# Esquematico.net
KiCad netlist of a schematic drawn in Altium Designer
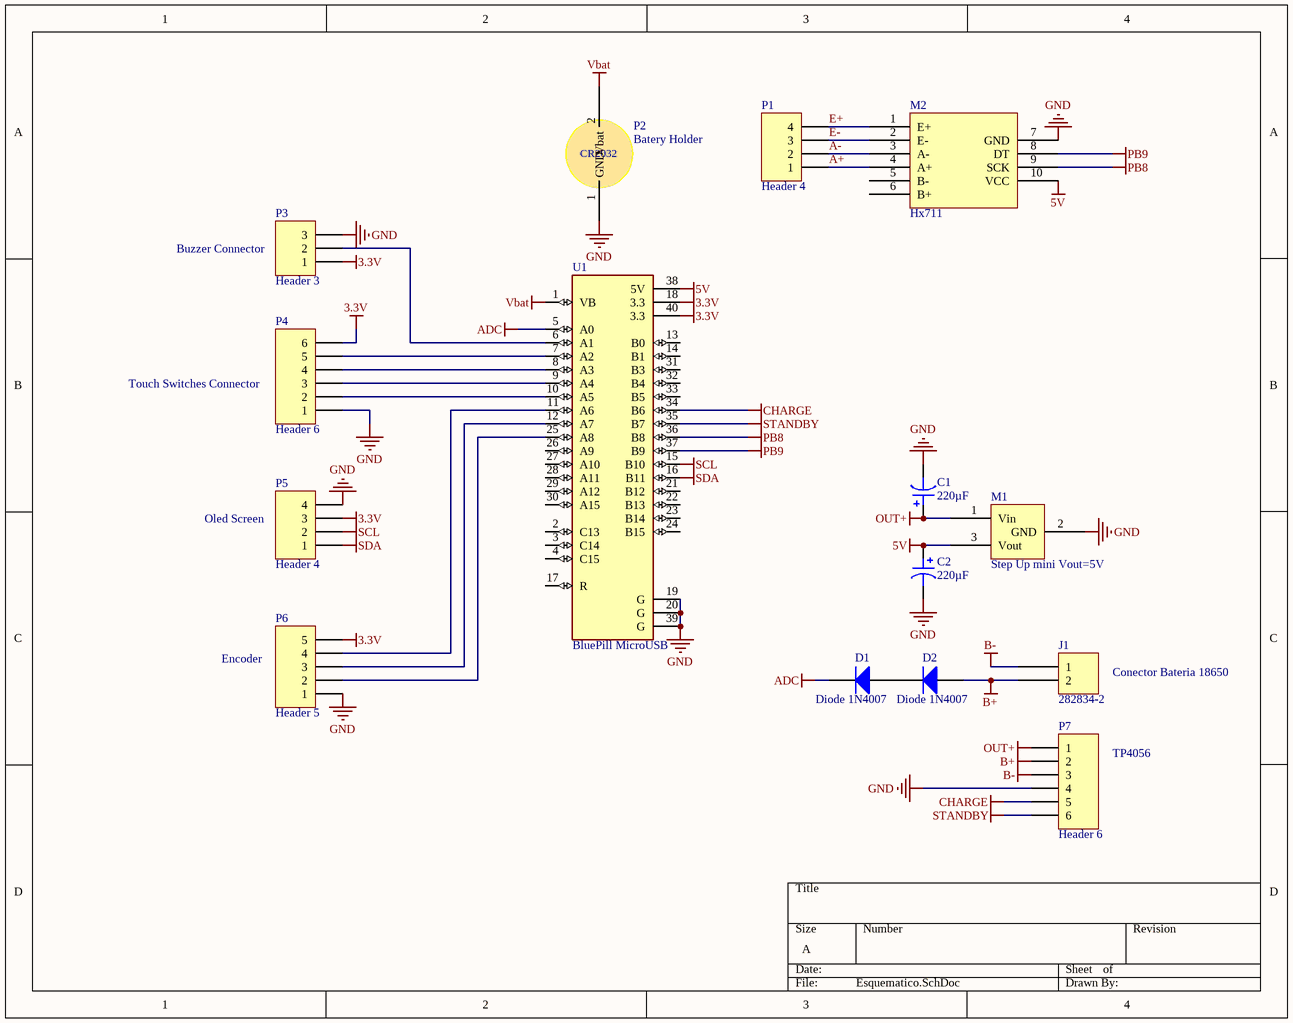
[diagram p0: Esquematico.SchDoc]

(export (version "E")
  (design (tool "Eeschema 10.0.6"))
  (components
    (comp (ref "C1")
      (value "220µF")
      (footprint "CAP TH ALUM ELEC D10.00mm S5.00mm H12.50mm")
      (description "CAP ALUM 220UF 20% 50V RADIAL")
      (fields (field (name "PART NUMBER") "UVZ1H221MPD") (field (name "MANUFACTURER") "Nichicon"))
      (libsource (lib "Celestial Altium Library - altium_library") (part "Polarised Capacitor"))
    )
    (comp (ref "C2")
      (value "220µF")
      (footprint "CAP TH ALUM ELEC D10.00mm S5.00mm H12.50mm")
      (description "CAP ALUM 220UF 20% 50V RADIAL")
      (fields (field (name "PART NUMBER") "UVZ1H221MPD") (field (name "MANUFACTURER") "Nichicon"))
      (libsource (lib "Celestial Altium Library - altium_library") (part "Polarised Capacitor"))
    )
    (comp (ref "D1")
      (value "Diode 1N4007")
      (footprint "DO-41")
      (description "1 Amp General Purpose Rectifier")
      (fields (field (name "PUBLISHER") "Altium Limited"))
      (libsource (lib "Miscellaneous Devices") (part "Diode 1N4007"))
    )
    (comp (ref "D2")
      (value "Diode 1N4007")
      (footprint "DO-41")
      (description "1 Amp General Purpose Rectifier")
      (fields (field (name "PUBLISHER") "Altium Limited"))
      (libsource (lib "Miscellaneous Devices") (part "Diode 1N4007"))
    )
    (comp (ref "J1")
      (value "282834-2")
      (footprint "TE 282834-2")
      (description "TERM BLK 2P SIDE ENT 2.54MM PCB")
      (fields (field (name "MANUFACTURER") "TE Connectivity AMP Connectors") (field (name "VOLTAGE") "150V"))
      (libsource (lib "Celestial Altium Library - altium_library") (part "2 Pin"))
    )
    (comp (ref "M1")
      (value "Step Up mini Vout=5V")
      (footprint "StepUp Mini 5V")
      (libsource (lib "BateryHolder") (part "StepUp 5V"))
    )
    (comp (ref "M2") (value "Hx711") (footprint "HX711") (libsource (lib "modulos") (part "Hx711")))
    (comp (ref "P1")
      (value "Header 4")
      (footprint "HDR1X4")
      (description "Header, 4-Pin")
      (fields (field (name "PUBLISHER") "Altium Limited"))
      (libsource (lib "Miscellaneous Connectors") (part "Header 4"))
    )
    (comp (ref "P2")
      (value "Batery Holder")
      (footprint "20mm Cell Holder")
      (libsource (lib "BateryHolder") (part "Component_1"))
    )
    (comp (ref "P3")
      (value "Header 3")
      (footprint "HDR1X3")
      (description "Header, 3-Pin")
      (fields (field (name "PUBLISHER") "Altium Limited"))
      (libsource (lib "Miscellaneous Connectors") (part "Header 3"))
    )
    (comp (ref "P4")
      (value "Header 6")
      (footprint "HDR1X6")
      (description "Header, 6-Pin")
      (fields (field (name "PUBLISHER") "Altium Limited"))
      (libsource (lib "") (part "Header 6_1"))
    )
    (comp (ref "P5")
      (value "Header 4")
      (footprint "HDR1X4")
      (description "Header, 4-Pin")
      (fields (field (name "PUBLISHER") "Altium Limited"))
      (libsource (lib "Miscellaneous Connectors") (part "Header 4"))
    )
    (comp (ref "P6")
      (value "Header 5")
      (footprint "HDR1X5")
      (description "Header, 5-Pin")
      (fields (field (name "PUBLISHER") "Altium Limited"))
      (libsource (lib "Miscellaneous Connectors") (part "Header 5"))
    )
    (comp (ref "P7")
      (value "Header 6")
      (footprint "HDR1X6")
      (description "Header, 6-Pin")
      (fields (field (name "PUBLISHER") "Altium Limited"))
      (libsource (lib "Miscellaneous Connectors") (part "Header 6"))
    )
    (comp (ref "U1")
      (value "BluePill MicroUSB")
      (footprint "MODULE_ZC323000")
      (description "STM32F103C8T6 ARM STM32 Minimum System Development Board Module For Arduino")
      (fields (field (name "MP") "ZC323000"))
      (libsource (lib "Bluepill") (part "ZC323000"))
    )
  )
  (nets
    (net (code "1") (name "/A+") (class "Default")
      (node (ref "M2") (pin "4") (pinfunction "A+_4") (pintype "passive"))
      (node (ref "P1") (pin "1") (pinfunction "1_1") (pintype "passive"))
    )
    (net (code "2") (name "/A-") (class "Default")
      (node (ref "M2") (pin "3") (pinfunction "A-_3") (pintype "passive"))
      (node (ref "P1") (pin "2") (pinfunction "2_2") (pintype "passive"))
    )
    (net (code "3") (name "/E+") (class "Default")
      (node (ref "M2") (pin "1") (pinfunction "E+_1") (pintype "passive"))
      (node (ref "P1") (pin "4") (pinfunction "4_4") (pintype "passive"))
    )
    (net (code "4") (name "/E-") (class "Default")
      (node (ref "M2") (pin "2") (pinfunction "E-_2") (pintype "passive"))
      (node (ref "P1") (pin "3") (pinfunction "3_3") (pintype "passive"))
    )
    (net (code "5") (name "3.3V") (class "Default")
      (node (ref "P3") (pin "1") (pinfunction "1_1") (pintype "passive"))
      (node (ref "P4") (pin "6") (pinfunction "6_6") (pintype "passive"))
      (node (ref "P5") (pin "3") (pinfunction "3_3") (pintype "passive"))
      (node (ref "P6") (pin "5") (pinfunction "5_5") (pintype "passive"))
      (node (ref "U1") (pin "18") (pinfunction "3.3_18") (pintype "power_in"))
      (node (ref "U1") (pin "40") (pinfunction "3.3_40") (pintype "power_in"))
    )
    (net (code "6") (name "5V") (class "Default")
      (node (ref "C2") (pin "1") (pinfunction "1_1") (pintype "passive"))
      (node (ref "M1") (pin "3") (pinfunction "Vout_3") (pintype "passive"))
      (node (ref "M2") (pin "10") (pinfunction "VCC_10") (pintype "passive"))
      (node (ref "U1") (pin "38") (pinfunction "5V_38") (pintype "power_in"))
    )
    (net (code "7") (name "ADC") (class "Default")
      (node (ref "D1") (pin "2") (pinfunction "K_2") (pintype "passive"))
      (node (ref "U1") (pin "5") (pinfunction "A0_5") (pintype "bidirectional"))
    )
    (net (code "8") (name "B+") (class "Default")
      (node (ref "D2") (pin "1") (pinfunction "A_1") (pintype "passive"))
      (node (ref "J1") (pin "2") (pinfunction "2_2") (pintype "passive"))
      (node (ref "P7") (pin "2") (pinfunction "2_2") (pintype "passive"))
    )
    (net (code "9") (name "B-") (class "Default")
      (node (ref "J1") (pin "1") (pinfunction "1_1") (pintype "passive"))
      (node (ref "P7") (pin "3") (pinfunction "3_3") (pintype "passive"))
    )
    (net (code "10") (name "CHARGE") (class "Default")
      (node (ref "P7") (pin "5") (pinfunction "5_5") (pintype "passive"))
      (node (ref "U1") (pin "34") (pinfunction "B6_34") (pintype "bidirectional"))
    )
    (net (code "11") (name "GND") (class "Default")
      (node (ref "C1") (pin "2") (pinfunction "2_2") (pintype "passive"))
      (node (ref "C2") (pin "2") (pinfunction "2_2") (pintype "passive"))
      (node (ref "M1") (pin "2") (pinfunction "GND_2") (pintype "passive"))
      (node (ref "M2") (pin "7") (pinfunction "GND_7") (pintype "passive"))
      (node (ref "P2") (pin "1") (pinfunction "GND_1") (pintype "passive"))
      (node (ref "P3") (pin "3") (pinfunction "3_3") (pintype "passive"))
      (node (ref "P4") (pin "1") (pinfunction "1_1") (pintype "passive"))
      (node (ref "P5") (pin "4") (pinfunction "4_4") (pintype "passive"))
      (node (ref "P6") (pin "1") (pinfunction "1_1") (pintype "passive"))
      (node (ref "P7") (pin "4") (pinfunction "4_4") (pintype "passive"))
      (node (ref "U1") (pin "19") (pinfunction "G_19") (pintype "power_in"))
      (node (ref "U1") (pin "20") (pinfunction "G_20") (pintype "power_in"))
      (node (ref "U1") (pin "39") (pinfunction "G_39") (pintype "power_in"))
    )
    (net (code "12") (name "Net-(D1-A)") (class "Default")
      (node (ref "D1") (pin "1") (pinfunction "A_1") (pintype "passive"))
      (node (ref "D2") (pin "2") (pinfunction "K_2") (pintype "passive"))
    )
    (net (code "13") (name "Net-(U1-A1)") (class "Default")
      (node (ref "P3") (pin "2") (pinfunction "2_2") (pintype "passive"))
      (node (ref "U1") (pin "6") (pinfunction "A1_6") (pintype "bidirectional"))
    )
    (net (code "14") (name "Net-(U1-A2)") (class "Default")
      (node (ref "P4") (pin "5") (pinfunction "5_5") (pintype "passive"))
      (node (ref "U1") (pin "7") (pinfunction "A2_7") (pintype "bidirectional"))
    )
    (net (code "15") (name "Net-(U1-A3)") (class "Default")
      (node (ref "P4") (pin "4") (pinfunction "4_4") (pintype "passive"))
      (node (ref "U1") (pin "8") (pinfunction "A3_8") (pintype "bidirectional"))
    )
    (net (code "16") (name "Net-(U1-A4)") (class "Default")
      (node (ref "P4") (pin "3") (pinfunction "3_3") (pintype "passive"))
      (node (ref "U1") (pin "9") (pinfunction "A4_9") (pintype "bidirectional"))
    )
    (net (code "17") (name "Net-(U1-A5)") (class "Default")
      (node (ref "P4") (pin "2") (pinfunction "2_2") (pintype "passive"))
      (node (ref "U1") (pin "10") (pinfunction "A5_10") (pintype "bidirectional"))
    )
    (net (code "18") (name "Net-(U1-A6)") (class "Default")
      (node (ref "P6") (pin "4") (pinfunction "4_4") (pintype "passive"))
      (node (ref "U1") (pin "11") (pinfunction "A6_11") (pintype "bidirectional"))
    )
    (net (code "19") (name "Net-(U1-A7)") (class "Default")
      (node (ref "P6") (pin "3") (pinfunction "3_3") (pintype "passive"))
      (node (ref "U1") (pin "12") (pinfunction "A7_12") (pintype "bidirectional"))
    )
    (net (code "20") (name "Net-(U1-A8)") (class "Default")
      (node (ref "P6") (pin "2") (pinfunction "2_2") (pintype "passive"))
      (node (ref "U1") (pin "25") (pinfunction "A8_25") (pintype "bidirectional"))
    )
    (net (code "21") (name "OUT+") (class "Default")
      (node (ref "C1") (pin "1") (pinfunction "1_1") (pintype "passive"))
      (node (ref "M1") (pin "1") (pinfunction "Vin_1") (pintype "passive"))
      (node (ref "P7") (pin "1") (pinfunction "1_1") (pintype "passive"))
    )
    (net (code "22") (name "PB8") (class "Default")
      (node (ref "M2") (pin "9") (pinfunction "SCK_9") (pintype "passive"))
      (node (ref "U1") (pin "36") (pinfunction "B8_36") (pintype "bidirectional"))
    )
    (net (code "23") (name "PB9") (class "Default")
      (node (ref "M2") (pin "8") (pinfunction "DT_8") (pintype "passive"))
      (node (ref "U1") (pin "37") (pinfunction "B9_37") (pintype "bidirectional"))
    )
    (net (code "24") (name "SCL") (class "Default")
      (node (ref "P5") (pin "2") (pinfunction "2_2") (pintype "passive"))
      (node (ref "U1") (pin "15") (pinfunction "B10_15") (pintype "bidirectional"))
    )
    (net (code "25") (name "SDA") (class "Default")
      (node (ref "P5") (pin "1") (pinfunction "1_1") (pintype "passive"))
      (node (ref "U1") (pin "16") (pinfunction "B11_16") (pintype "bidirectional"))
    )
    (net (code "26") (name "STANDBY") (class "Default")
      (node (ref "P7") (pin "6") (pinfunction "6_6") (pintype "passive"))
      (node (ref "U1") (pin "35") (pinfunction "B7_35") (pintype "bidirectional"))
    )
    (net (code "27") (name "Vbat") (class "Default")
      (node (ref "P2") (pin "2") (pinfunction "Vbat_2") (pintype "passive"))
      (node (ref "U1") (pin "1") (pinfunction "VB_1") (pintype "bidirectional"))
    )
    (net (code "28") (name "unconnected-(M2-B+-Pad6)") (class "Default")
      (node (ref "M2") (pin "6") (pinfunction "B+_6") (pintype "passive"))
    )
    (net (code "29") (name "unconnected-(M2-B--Pad5)") (class "Default")
      (node (ref "M2") (pin "5") (pinfunction "B-_5") (pintype "passive"))
    )
    (net (code "30") (name "unconnected-(U1-A9-Pad26)") (class "Default")
      (node (ref "U1") (pin "26") (pinfunction "A9_26") (pintype "bidirectional"))
    )
    (net (code "31") (name "unconnected-(U1-A10-Pad27)") (class "Default")
      (node (ref "U1") (pin "27") (pinfunction "A10_27") (pintype "bidirectional"))
    )
    (net (code "32") (name "unconnected-(U1-A11-Pad28)") (class "Default")
      (node (ref "U1") (pin "28") (pinfunction "A11_28") (pintype "bidirectional"))
    )
    (net (code "33") (name "unconnected-(U1-A12-Pad29)") (class "Default")
      (node (ref "U1") (pin "29") (pinfunction "A12_29") (pintype "bidirectional"))
    )
    (net (code "34") (name "unconnected-(U1-A15-Pad30)") (class "Default")
      (node (ref "U1") (pin "30") (pinfunction "A15_30") (pintype "bidirectional"))
    )
    (net (code "35") (name "unconnected-(U1-B0-Pad13)") (class "Default")
      (node (ref "U1") (pin "13") (pinfunction "B0_13") (pintype "bidirectional"))
    )
    (net (code "36") (name "unconnected-(U1-B1-Pad14)") (class "Default")
      (node (ref "U1") (pin "14") (pinfunction "B1_14") (pintype "bidirectional"))
    )
    (net (code "37") (name "unconnected-(U1-B3-Pad31)") (class "Default")
      (node (ref "U1") (pin "31") (pinfunction "B3_31") (pintype "bidirectional"))
    )
    (net (code "38") (name "unconnected-(U1-B4-Pad32)") (class "Default")
      (node (ref "U1") (pin "32") (pinfunction "B4_32") (pintype "bidirectional"))
    )
    (net (code "39") (name "unconnected-(U1-B5-Pad33)") (class "Default")
      (node (ref "U1") (pin "33") (pinfunction "B5_33") (pintype "bidirectional"))
    )
    (net (code "40") (name "unconnected-(U1-B12-Pad21)") (class "Default")
      (node (ref "U1") (pin "21") (pinfunction "B12_21") (pintype "bidirectional"))
    )
    (net (code "41") (name "unconnected-(U1-B13-Pad22)") (class "Default")
      (node (ref "U1") (pin "22") (pinfunction "B13_22") (pintype "bidirectional"))
    )
    (net (code "42") (name "unconnected-(U1-B14-Pad23)") (class "Default")
      (node (ref "U1") (pin "23") (pinfunction "B14_23") (pintype "bidirectional"))
    )
    (net (code "43") (name "unconnected-(U1-B15-Pad24)") (class "Default")
      (node (ref "U1") (pin "24") (pinfunction "B15_24") (pintype "bidirectional"))
    )
    (net (code "44") (name "unconnected-(U1-C13-Pad2)") (class "Default")
      (node (ref "U1") (pin "2") (pinfunction "C13_2") (pintype "bidirectional"))
    )
    (net (code "45") (name "unconnected-(U1-C14-Pad3)") (class "Default")
      (node (ref "U1") (pin "3") (pinfunction "C14_3") (pintype "bidirectional"))
    )
    (net (code "46") (name "unconnected-(U1-C15-Pad4)") (class "Default")
      (node (ref "U1") (pin "4") (pinfunction "C15_4") (pintype "bidirectional"))
    )
    (net (code "47") (name "unconnected-(U1-R-Pad17)") (class "Default")
      (node (ref "U1") (pin "17") (pinfunction "R_17") (pintype "bidirectional"))
    )
  )
)
